# MPU.net
KiCad netlist of a schematic drawn in Altium Designer
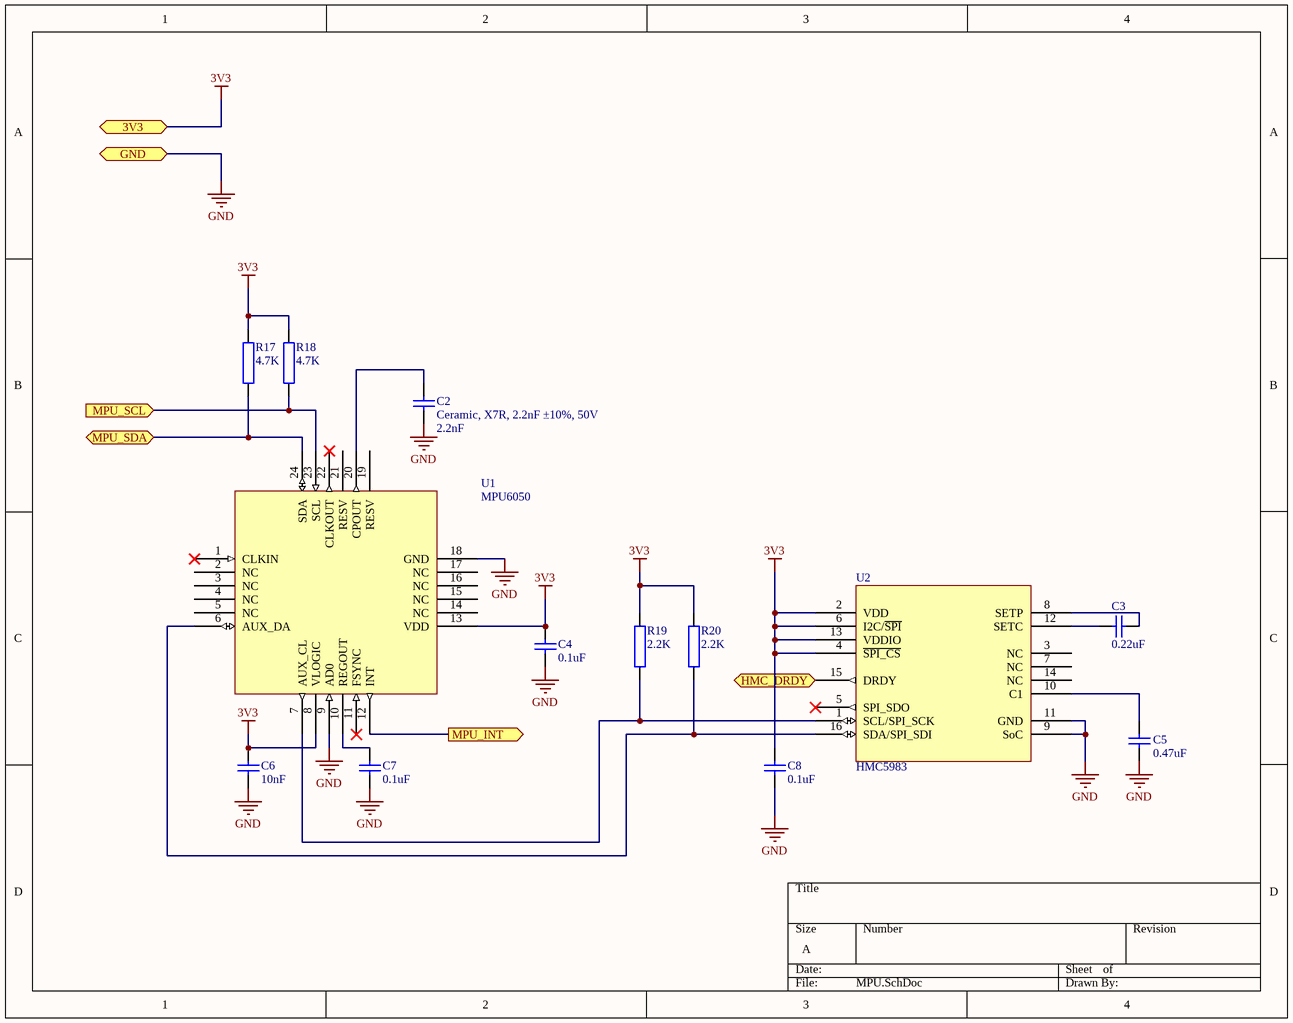
[diagram p0: MPU.SchDoc]

(export (version "E")
  (design (tool "Eeschema 10.0.6"))
  (components
    (comp (ref "C2")
      (value "Ceramic, X7R, 2.2nF ±10%, 50V")
      (footprint "C0603")
      (description "Capacitor (Semiconductor SIM Model)")
      (fields (field (name "ALTIUM_VALUE") "2.2nF") (field (name "PUBLISHER") "Altium Limited"))
      (libsource (lib "Quadcopter") (part "Cap"))
    )
    (comp (ref "C3")
      (value "0.22uF")
      (footprint "C0603")
      (description "Capacitor (Semiconductor SIM Model)")
      (fields (field (name "PUBLISHER") "Altium Limited"))
      (libsource (lib "Quadcopter") (part "Cap"))
    )
    (comp (ref "C4")
      (value "0.1uF")
      (footprint "C0603")
      (description "Capacitor (Semiconductor SIM Model)")
      (fields (field (name "PUBLISHER") "Altium Limited"))
      (libsource (lib "Quadcopter") (part "Cap"))
    )
    (comp (ref "C5")
      (value "0.47uF")
      (footprint "C0603")
      (description "Capacitor (Semiconductor SIM Model)")
      (fields (field (name "PUBLISHER") "Altium Limited"))
      (libsource (lib "Quadcopter") (part "Cap"))
    )
    (comp (ref "C6")
      (value "10nF")
      (footprint "C0603")
      (description "Capacitor (Semiconductor SIM Model)")
      (fields (field (name "PUBLISHER") "Altium Limited"))
      (libsource (lib "Quadcopter") (part "Cap"))
    )
    (comp (ref "C7")
      (value "0.1uF")
      (footprint "C0603")
      (description "Capacitor (Semiconductor SIM Model)")
      (fields (field (name "PUBLISHER") "Altium Limited"))
      (libsource (lib "Quadcopter") (part "Cap"))
    )
    (comp (ref "C8")
      (value "0.1uF")
      (footprint "C0603")
      (description "Capacitor (Semiconductor SIM Model)")
      (fields (field (name "PUBLISHER") "Altium Limited"))
      (libsource (lib "Quadcopter") (part "Cap"))
    )
    (comp (ref "R17")
      (value "4.7K")
      (footprint "R0603")
      (description "Resistor")
      (fields (field (name "PUBLISHER") "Altium Limited"))
      (libsource (lib "Quadcopter") (part "Res3"))
    )
    (comp (ref "R18")
      (value "4.7K")
      (footprint "R0603")
      (description "Resistor")
      (fields (field (name "PUBLISHER") "Altium Limited"))
      (libsource (lib "Quadcopter") (part "Res3"))
    )
    (comp (ref "R19")
      (value "2.2K")
      (footprint "R0603")
      (description "Resistor")
      (fields (field (name "PUBLISHER") "Altium Limited"))
      (libsource (lib "Quadcopter") (part "Res3"))
    )
    (comp (ref "R20")
      (value "2.2K")
      (footprint "R0603")
      (description "Resistor")
      (fields (field (name "PUBLISHER") "Altium Limited"))
      (libsource (lib "Quadcopter") (part "Res3"))
    )
    (comp (ref "U1")
      (value "MPU6050")
      (footprint "24 Lead QFN")
      (description "MPU6050, 24pin")
      (libsource (lib "Quadcopter") (part "MPU6050"))
    )
    (comp (ref "U2")
      (value "HMC5983")
      (footprint "16 Lead QFN 2")
      (description "HMC5983, 16pin")
      (libsource (lib "Quadcopter") (part "HMC5983"))
    )
  )
  (nets
    (net (code "1") (name "/HMC_DRDY") (class "Default")
      (node (ref "U2") (pin "15") (pinfunction "DRDY_15") (pintype "output"))
    )
    (net (code "2") (name "/MPU_INT") (class "Default")
      (node (ref "U1") (pin "12") (pinfunction "INT_12") (pintype "output"))
    )
    (net (code "3") (name "/MPU_SCL") (class "Default")
      (node (ref "R18") (pin "1") (pinfunction "1_1") (pintype "passive"))
      (node (ref "U1") (pin "23") (pinfunction "SCL_23") (pintype "input"))
    )
    (net (code "4") (name "/MPU_SDA") (class "Default")
      (node (ref "R17") (pin "1") (pinfunction "1_1") (pintype "passive"))
      (node (ref "U1") (pin "24") (pinfunction "SDA_24") (pintype "bidirectional"))
    )
    (net (code "5") (name "3V3") (class "Default")
      (node (ref "C4") (pin "2") (pinfunction "2_2") (pintype "passive"))
      (node (ref "C6") (pin "2") (pinfunction "2_2") (pintype "passive"))
      (node (ref "C8") (pin "2") (pinfunction "2_2") (pintype "passive"))
      (node (ref "R17") (pin "2") (pinfunction "2_2") (pintype "passive"))
      (node (ref "R18") (pin "2") (pinfunction "2_2") (pintype "passive"))
      (node (ref "R19") (pin "2") (pinfunction "2_2") (pintype "passive"))
      (node (ref "R20") (pin "2") (pinfunction "2_2") (pintype "passive"))
      (node (ref "U1") (pin "13") (pinfunction "VDD_13") (pintype "passive"))
      (node (ref "U1") (pin "8") (pinfunction "VLOGIC_8") (pintype "passive"))
      (node (ref "U2") (pin "13") (pinfunction "VDDIO_13") (pintype "passive"))
      (node (ref "U2") (pin "2") (pinfunction "VDD_2") (pintype "passive"))
      (node (ref "U2") (pin "4") (pinfunction "~{SPI_CS}_4") (pintype "passive"))
      (node (ref "U2") (pin "6") (pinfunction "I2C/~{SPI}_6") (pintype "passive"))
    )
    (net (code "6") (name "GND") (class "Default")
      (node (ref "C2") (pin "1") (pinfunction "1_1") (pintype "passive"))
      (node (ref "C4") (pin "1") (pinfunction "1_1") (pintype "passive"))
      (node (ref "C5") (pin "1") (pinfunction "1_1") (pintype "passive"))
      (node (ref "C6") (pin "1") (pinfunction "1_1") (pintype "passive"))
      (node (ref "C7") (pin "1") (pinfunction "1_1") (pintype "passive"))
      (node (ref "C8") (pin "1") (pinfunction "1_1") (pintype "passive"))
      (node (ref "U1") (pin "18") (pinfunction "GND_18") (pintype "passive"))
      (node (ref "U1") (pin "9") (pinfunction "AD0_9") (pintype "input"))
      (node (ref "U2") (pin "11") (pinfunction "GND_11") (pintype "passive"))
      (node (ref "U2") (pin "9") (pinfunction "SoC_9") (pintype "passive"))
    )
    (net (code "7") (name "Net-(U1-AUX_CL)") (class "Default")
      (node (ref "R19") (pin "1") (pinfunction "1_1") (pintype "passive"))
      (node (ref "U1") (pin "7") (pinfunction "AUX_CL_7") (pintype "output"))
      (node (ref "U2") (pin "1") (pinfunction "SCL/SPI_SCK_1") (pintype "bidirectional"))
    )
    (net (code "8") (name "Net-(U1-AUX_DA)") (class "Default")
      (node (ref "R20") (pin "1") (pinfunction "1_1") (pintype "passive"))
      (node (ref "U1") (pin "6") (pinfunction "AUX_DA_6") (pintype "bidirectional"))
      (node (ref "U2") (pin "16") (pinfunction "SDA/SPI_SDI_16") (pintype "bidirectional"))
    )
    (net (code "9") (name "Net-(U1-CPOUT)") (class "Default")
      (node (ref "C2") (pin "2") (pinfunction "2_2") (pintype "passive"))
      (node (ref "U1") (pin "20") (pinfunction "CPOUT_20") (pintype "output"))
    )
    (net (code "10") (name "Net-(U1-REGOUT)") (class "Default")
      (node (ref "C7") (pin "2") (pinfunction "2_2") (pintype "passive"))
      (node (ref "U1") (pin "10") (pinfunction "REGOUT_10") (pintype "passive"))
    )
    (net (code "11") (name "Net-(U2-C1)") (class "Default")
      (node (ref "C5") (pin "2") (pinfunction "2_2") (pintype "passive"))
      (node (ref "U2") (pin "10") (pinfunction "C1_10") (pintype "passive"))
    )
    (net (code "12") (name "Net-(U2-SETC)") (class "Default")
      (node (ref "C3") (pin "2") (pinfunction "2_2") (pintype "passive"))
      (node (ref "U2") (pin "12") (pinfunction "SETC_12") (pintype "passive"))
    )
    (net (code "13") (name "Net-(U2-SETP)") (class "Default")
      (node (ref "C3") (pin "1") (pinfunction "1_1") (pintype "passive"))
      (node (ref "U2") (pin "8") (pinfunction "SETP_8") (pintype "passive"))
    )
    (net (code "14") (name "unconnected-(U1-CLKIN-Pad1)") (class "Default")
      (node (ref "U1") (pin "1") (pinfunction "CLKIN_1") (pintype "input+no_connect"))
    )
    (net (code "15") (name "unconnected-(U1-CLKOUT-Pad22)") (class "Default")
      (node (ref "U1") (pin "22") (pinfunction "CLKOUT_22") (pintype "output+no_connect"))
    )
    (net (code "16") (name "unconnected-(U1-FSYNC-Pad11)") (class "Default")
      (node (ref "U1") (pin "11") (pinfunction "FSYNC_11") (pintype "input+no_connect"))
    )
    (net (code "17") (name "unconnected-(U1-NC-Pad2)") (class "Default")
      (node (ref "U1") (pin "2") (pinfunction "NC_2") (pintype "passive"))
    )
    (net (code "18") (name "unconnected-(U1-NC-Pad3)") (class "Default")
      (node (ref "U1") (pin "3") (pinfunction "NC_3") (pintype "passive"))
    )
    (net (code "19") (name "unconnected-(U1-NC-Pad4)") (class "Default")
      (node (ref "U1") (pin "4") (pinfunction "NC_4") (pintype "passive"))
    )
    (net (code "20") (name "unconnected-(U1-NC-Pad5)") (class "Default")
      (node (ref "U1") (pin "5") (pinfunction "NC_5") (pintype "passive"))
    )
    (net (code "21") (name "unconnected-(U1-NC-Pad14)") (class "Default")
      (node (ref "U1") (pin "14") (pinfunction "NC_14") (pintype "passive"))
    )
    (net (code "22") (name "unconnected-(U1-NC-Pad15)") (class "Default")
      (node (ref "U1") (pin "15") (pinfunction "NC_15") (pintype "passive"))
    )
    (net (code "23") (name "unconnected-(U1-NC-Pad16)") (class "Default")
      (node (ref "U1") (pin "16") (pinfunction "NC_16") (pintype "passive"))
    )
    (net (code "24") (name "unconnected-(U1-NC-Pad17)") (class "Default")
      (node (ref "U1") (pin "17") (pinfunction "NC_17") (pintype "passive"))
    )
    (net (code "25") (name "unconnected-(U1-RESV-Pad19)") (class "Default")
      (node (ref "U1") (pin "19") (pinfunction "RESV_19") (pintype "passive"))
    )
    (net (code "26") (name "unconnected-(U1-RESV-Pad21)") (class "Default")
      (node (ref "U1") (pin "21") (pinfunction "RESV_21") (pintype "passive"))
    )
    (net (code "27") (name "unconnected-(U2-NC-Pad3)") (class "Default")
      (node (ref "U2") (pin "3") (pinfunction "NC_3") (pintype "passive"))
    )
    (net (code "28") (name "unconnected-(U2-NC-Pad7)") (class "Default")
      (node (ref "U2") (pin "7") (pinfunction "NC_7") (pintype "passive"))
    )
    (net (code "29") (name "unconnected-(U2-NC-Pad14)") (class "Default")
      (node (ref "U2") (pin "14") (pinfunction "NC_14") (pintype "passive"))
    )
    (net (code "30") (name "unconnected-(U2-SPI_SDO-Pad5)") (class "Default")
      (node (ref "U2") (pin "5") (pinfunction "SPI_SDO_5") (pintype "output+no_connect"))
    )
  )
)
